# Section3_HW1_Justin_Ngo_u0453732_MotorPC.net
KiCad netlist of a schematic drawn in EAGLE
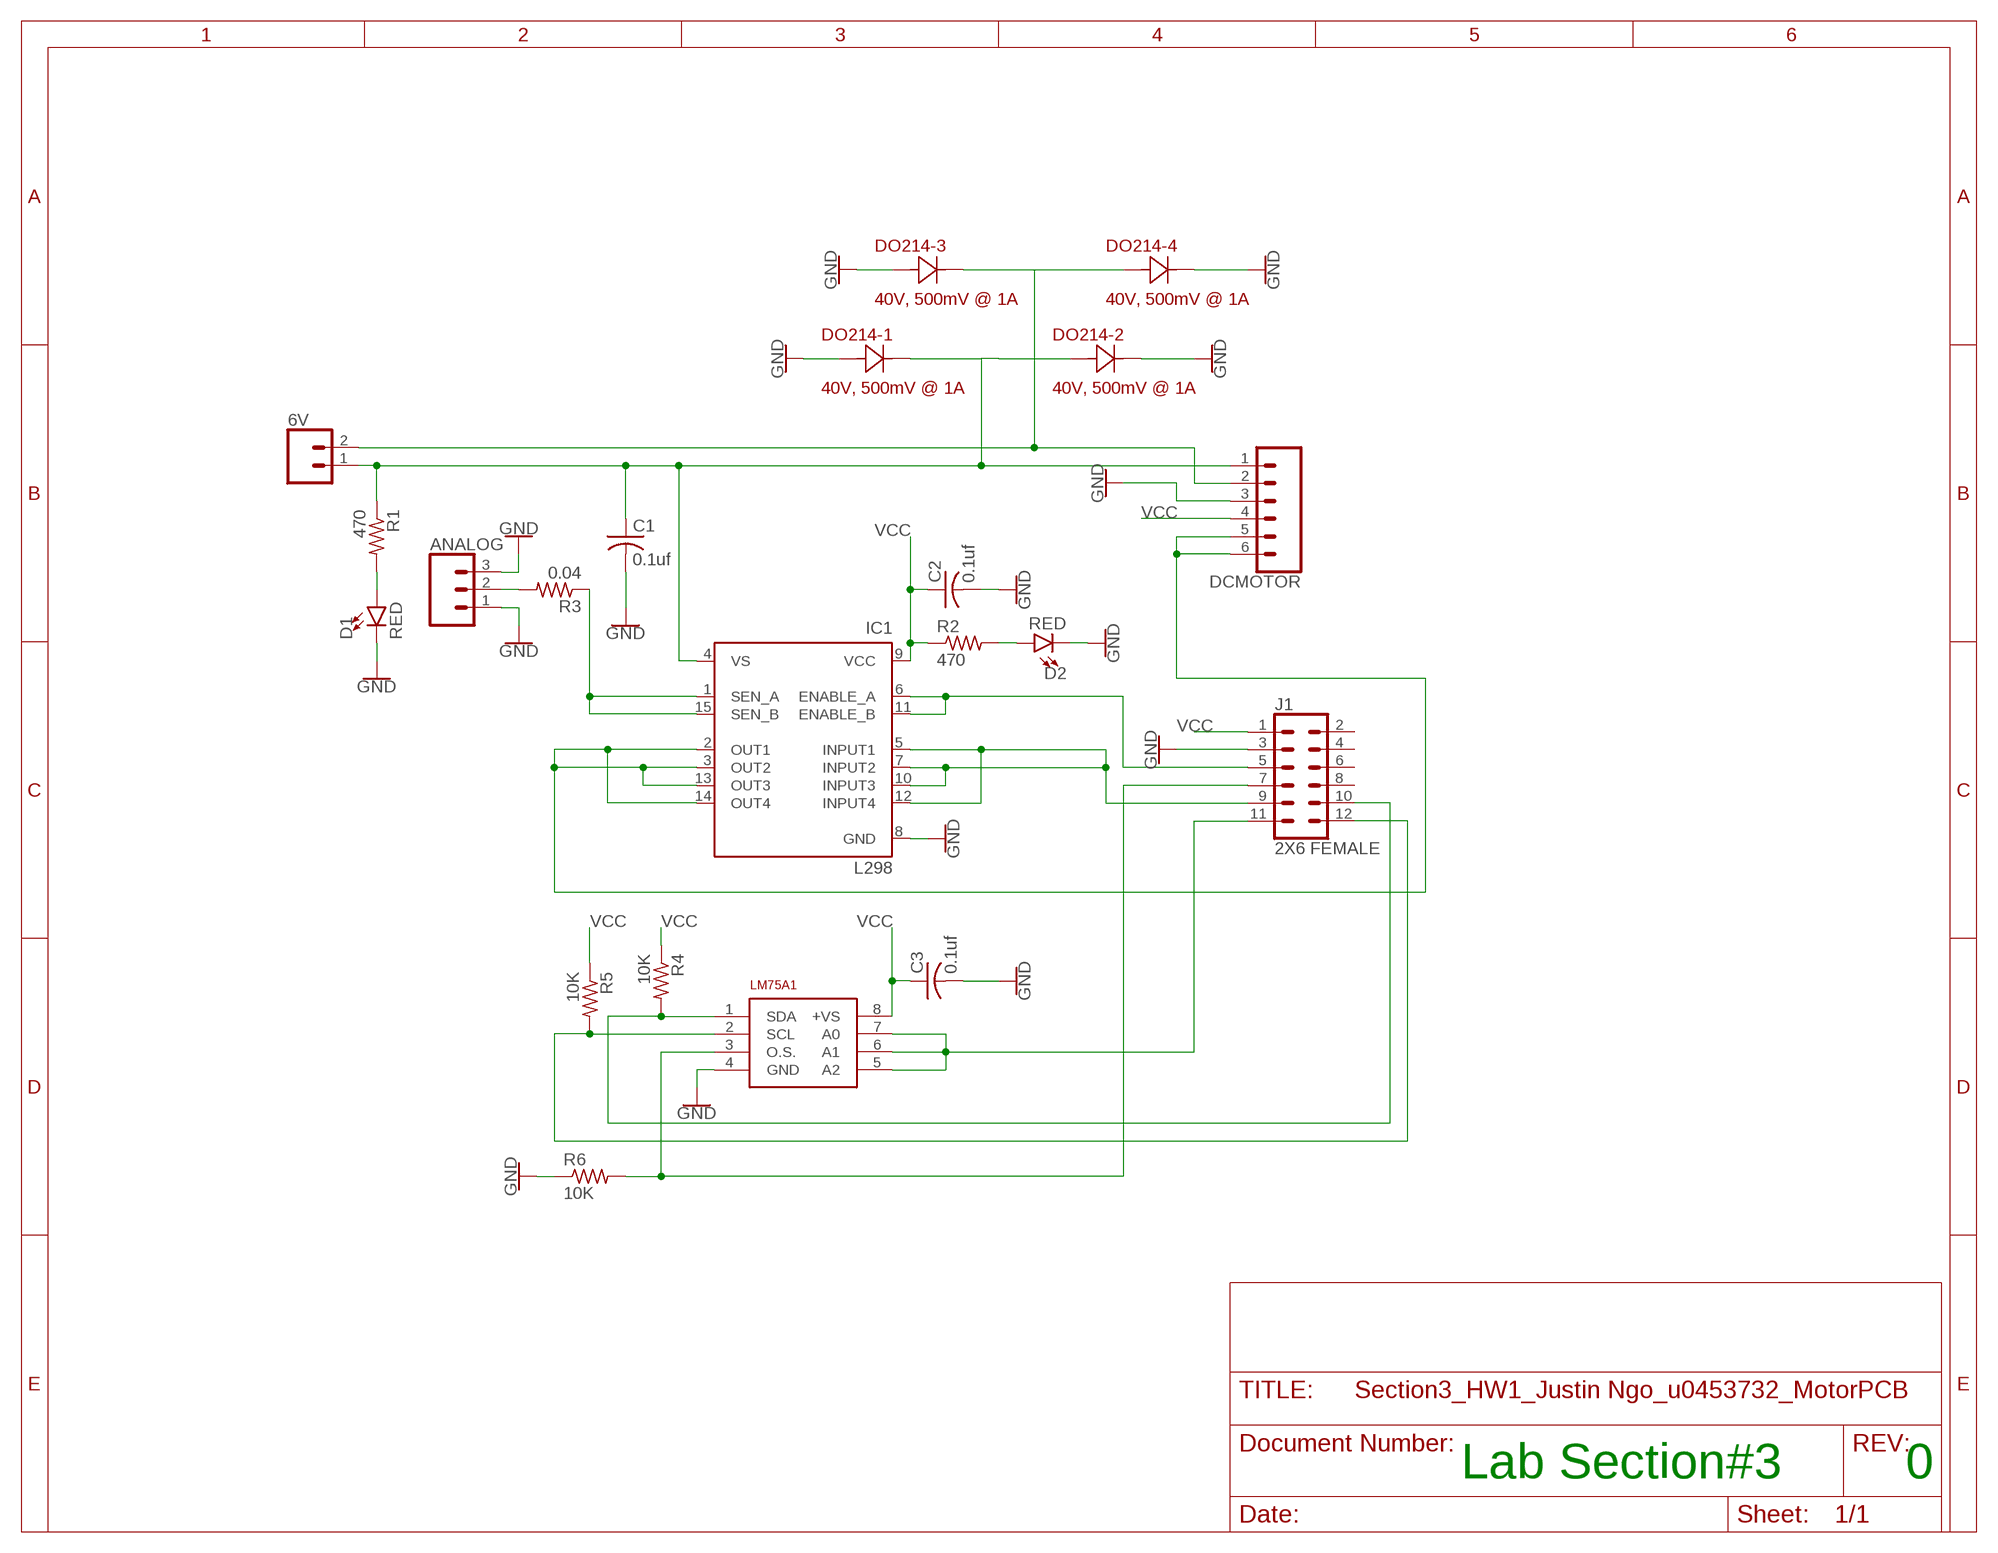
[diagram p0: schematic, sheet 1]

(export (version "E")
  (design (tool "Eeschema 10.0.6"))
  (components
    (comp (ref "6V")
      (value "CONN_025MM")
      (footprint "eagle-import:SCREWTERMINAL-5MM-2")
      (libsource (lib "eagle-import") (part "CONN_025MM"))
    )
    (comp (ref "ANALOG")
      (value "CONN_03")
      (footprint "eagle-import:1X03")
      (libsource (lib "eagle-import") (part "CONN_03"))
    )
    (comp (ref "C1")
      (value "0.1uf")
      (footprint "eagle-import:C1206")
      (libsource (lib "eagle-import") (part "C-USC1206"))
    )
    (comp (ref "C2")
      (value "0.1uf")
      (footprint "eagle-import:C1206")
      (libsource (lib "eagle-import") (part "C-USC1206"))
    )
    (comp (ref "C3")
      (value "0.1uf")
      (footprint "eagle-import:C1206")
      (libsource (lib "eagle-import") (part "C-USC1206"))
    )
    (comp (ref "D1")
      (value "RED")
      (footprint "eagle-import:LED-1206")
      (libsource (lib "eagle-import") (part "LED-RED1206"))
    )
    (comp (ref "D2")
      (value "RED")
      (footprint "eagle-import:LED-1206")
      (libsource (lib "eagle-import") (part "LED-RED1206"))
    )
    (comp (ref "DCMOTOR")
      (value "CONN_06LOCK_LONGPADS")
      (footprint "eagle-import:1X06_LOCK_LONGPADS")
      (libsource (lib "eagle-import") (part "CONN_06LOCK_LONGPADS"))
    )
    (comp (ref "DO214-1")
      (value "40V, 500mV @ 1A")
      (footprint "eagle-import:DIODE_DO214AC")
      (fields
        (field (name "MANUFACTURER_PART_NUMBER") "SS14")
        (field (name "RSPARTNUMBER") "4470352")
        (field (name "COPYRIGHT") "Copyright C 2015 Accelerated Designs. All rights reserved")
      )
      (libsource (lib "eagle-import") (part "SS14"))
    )
    (comp (ref "DO214-2")
      (value "40V, 500mV @ 1A")
      (footprint "eagle-import:DIODE_DO214AC")
      (fields
        (field (name "MANUFACTURER_PART_NUMBER") "SS14")
        (field (name "RSPARTNUMBER") "4470352")
        (field (name "COPYRIGHT") "Copyright C 2015 Accelerated Designs. All rights reserved")
      )
      (libsource (lib "eagle-import") (part "SS14"))
    )
    (comp (ref "DO214-3")
      (value "40V, 500mV @ 1A")
      (footprint "eagle-import:DIODE_DO214AC")
      (fields
        (field (name "MANUFACTURER_PART_NUMBER") "SS14")
        (field (name "RSPARTNUMBER") "4470352")
        (field (name "COPYRIGHT") "Copyright C 2015 Accelerated Designs. All rights reserved")
      )
      (libsource (lib "eagle-import") (part "SS14"))
    )
    (comp (ref "DO214-4")
      (value "40V, 500mV @ 1A")
      (footprint "eagle-import:DIODE_DO214AC")
      (fields
        (field (name "MANUFACTURER_PART_NUMBER") "SS14")
        (field (name "RSPARTNUMBER") "4470352")
        (field (name "COPYRIGHT") "Copyright C 2015 Accelerated Designs. All rights reserved")
      )
      (libsource (lib "eagle-import") (part "SS14"))
    )
    (comp (ref "IC1")
      (value "L298")
      (footprint "eagle-import:MULTIWATT-15")
      (fields (field (name "MPN") "L298N"))
      (libsource (lib "eagle-import") (part "L298"))
    )
    (comp (ref "J1")
      (value "2X6 FEMALE")
      (footprint "eagle-import:2X6")
      (libsource (lib "eagle-import") (part "CONN_06X2PTH_FEMALE"))
    )
    (comp (ref "LM75A1")
      (value "TI-LM75A")
      (footprint "eagle-import:TI-LM75A")
      (libsource (lib "eagle-import") (part "TI-LM75A"))
    )
    (comp (ref "R1")
      (value "470")
      (footprint "eagle-import:R1206")
      (libsource (lib "eagle-import") (part "R-US_R1206"))
    )
    (comp (ref "R2")
      (value "470")
      (footprint "eagle-import:R1206")
      (libsource (lib "eagle-import") (part "R-US_R1206"))
    )
    (comp (ref "R3")
      (value "0.04")
      (footprint "eagle-import:R1206")
      (libsource (lib "eagle-import") (part "R-US_R1206"))
    )
    (comp (ref "R4")
      (value "10K")
      (footprint "eagle-import:R1206")
      (libsource (lib "eagle-import") (part "R-US_R1206"))
    )
    (comp (ref "R5")
      (value "10K")
      (footprint "eagle-import:R1206")
      (libsource (lib "eagle-import") (part "R-US_R1206"))
    )
    (comp (ref "R6")
      (value "10K")
      (footprint "eagle-import:R1206")
      (libsource (lib "eagle-import") (part "R-US_R1206"))
    )
  )
  (nets
    (net (code "1") (name "/VCC") (class "Default")
      (node (ref "C2") (pin "1") (pinfunction "1_1") (pintype "passive"))
      (node (ref "C3") (pin "1") (pinfunction "1_1") (pintype "passive"))
      (node (ref "DCMOTOR") (pin "4") (pinfunction "4_4") (pintype "passive"))
      (node (ref "IC1") (pin "9") (pinfunction "VCC_9") (pintype "power_in"))
      (node (ref "J1") (pin "1") (pinfunction "1_1") (pintype "passive"))
      (node (ref "LM75A1") (pin "8") (pinfunction "+VS_8") (pintype "bidirectional"))
      (node (ref "R2") (pin "1") (pinfunction "1_1") (pintype "passive"))
      (node (ref "R4") (pin "1") (pinfunction "1_1") (pintype "passive"))
      (node (ref "R5") (pin "1") (pinfunction "1_1") (pintype "passive"))
    )
    (net (code "2") (name "GND") (class "Default")
      (node (ref "ANALOG") (pin "1") (pinfunction "1_1") (pintype "passive"))
      (node (ref "ANALOG") (pin "3") (pinfunction "3_3") (pintype "passive"))
      (node (ref "C1") (pin "2") (pinfunction "2_2") (pintype "passive"))
      (node (ref "C2") (pin "2") (pinfunction "2_2") (pintype "passive"))
      (node (ref "C3") (pin "2") (pinfunction "2_2") (pintype "passive"))
      (node (ref "D1") (pin "C") (pinfunction "C_C") (pintype "passive"))
      (node (ref "D2") (pin "C") (pinfunction "C_C") (pintype "passive"))
      (node (ref "DCMOTOR") (pin "3") (pinfunction "3_3") (pintype "passive"))
      (node (ref "DO214-1") (pin "2") (pinfunction "21_2") (pintype "passive"))
      (node (ref "DO214-2") (pin "1") (pinfunction "12_1") (pintype "passive"))
      (node (ref "DO214-3") (pin "2") (pinfunction "21_2") (pintype "passive"))
      (node (ref "DO214-4") (pin "1") (pinfunction "12_1") (pintype "passive"))
      (node (ref "IC1") (pin "8") (pinfunction "GND_8") (pintype "power_in"))
      (node (ref "J1") (pin "3") (pinfunction "3_3") (pintype "passive"))
      (node (ref "LM75A1") (pin "4") (pinfunction "GND_4") (pintype "bidirectional"))
      (node (ref "R6") (pin "1") (pinfunction "1_1") (pintype "passive"))
    )
    (net (code "3") (name "Net-(ANALOG-Pad2)") (class "Default")
      (node (ref "ANALOG") (pin "2") (pinfunction "2_2") (pintype "passive"))
      (node (ref "R3") (pin "2") (pinfunction "2_2") (pintype "passive"))
    )
    (net (code "4") (name "Net-(D1-PadA)") (class "Default")
      (node (ref "D1") (pin "A") (pinfunction "A_A") (pintype "passive"))
      (node (ref "R1") (pin "2") (pinfunction "2_2") (pintype "passive"))
    )
    (net (code "5") (name "Net-(D2-PadA)") (class "Default")
      (node (ref "D2") (pin "A") (pinfunction "A_A") (pintype "passive"))
      (node (ref "R2") (pin "2") (pinfunction "2_2") (pintype "passive"))
    )
    (net (code "6") (name "Net-(DO214-1-12)") (class "Default")
      (node (ref "6V") (pin "1") (pinfunction "1_1") (pintype "passive"))
      (node (ref "C1") (pin "1") (pinfunction "1_1") (pintype "passive"))
      (node (ref "DCMOTOR") (pin "1") (pinfunction "1_1") (pintype "passive"))
      (node (ref "DO214-1") (pin "1") (pinfunction "12_1") (pintype "passive"))
      (node (ref "DO214-2") (pin "2") (pinfunction "21_2") (pintype "passive"))
      (node (ref "IC1") (pin "4") (pinfunction "VS_4") (pintype "power_in"))
      (node (ref "R1") (pin "1") (pinfunction "1_1") (pintype "passive"))
    )
    (net (code "7") (name "Net-(DO214-3-12)") (class "Default")
      (node (ref "6V") (pin "2") (pinfunction "2_2") (pintype "passive"))
      (node (ref "DCMOTOR") (pin "2") (pinfunction "2_2") (pintype "passive"))
      (node (ref "DO214-3") (pin "1") (pinfunction "12_1") (pintype "passive"))
      (node (ref "DO214-4") (pin "2") (pinfunction "21_2") (pintype "passive"))
    )
    (net (code "8") (name "Net-(IC1-ENABLE_A)") (class "Default")
      (node (ref "IC1") (pin "11") (pinfunction "ENABLE_B_11") (pintype "input"))
      (node (ref "IC1") (pin "6") (pinfunction "ENABLE_A_6") (pintype "input"))
      (node (ref "J1") (pin "5") (pinfunction "5_5") (pintype "passive"))
    )
    (net (code "9") (name "Net-(IC1-INPUT1)") (class "Default")
      (node (ref "IC1") (pin "10") (pinfunction "INPUT3_10") (pintype "input"))
      (node (ref "IC1") (pin "12") (pinfunction "INPUT4_12") (pintype "input"))
      (node (ref "IC1") (pin "5") (pinfunction "INPUT1_5") (pintype "input"))
      (node (ref "IC1") (pin "7") (pinfunction "INPUT2_7") (pintype "input"))
      (node (ref "J1") (pin "9") (pinfunction "9_9") (pintype "passive"))
    )
    (net (code "10") (name "Net-(IC1-OUT1)") (class "Default")
      (node (ref "DCMOTOR") (pin "5") (pinfunction "5_5") (pintype "passive"))
      (node (ref "DCMOTOR") (pin "6") (pinfunction "6_6") (pintype "passive"))
      (node (ref "IC1") (pin "13") (pinfunction "OUT3_13") (pintype "output"))
      (node (ref "IC1") (pin "14") (pinfunction "OUT4_14") (pintype "output"))
      (node (ref "IC1") (pin "2") (pinfunction "OUT1_2") (pintype "output"))
      (node (ref "IC1") (pin "3") (pinfunction "OUT2_3") (pintype "output"))
    )
    (net (code "11") (name "Net-(IC1-SEN_A)") (class "Default")
      (node (ref "IC1") (pin "1") (pinfunction "SEN_A_1") (pintype "input"))
      (node (ref "IC1") (pin "15") (pinfunction "SEN_B_15") (pintype "input"))
      (node (ref "R3") (pin "1") (pinfunction "1_1") (pintype "passive"))
    )
    (net (code "12") (name "Net-(LM75A1-A0)") (class "Default")
      (node (ref "J1") (pin "11") (pinfunction "11_11") (pintype "passive"))
      (node (ref "LM75A1") (pin "5") (pinfunction "A2_5") (pintype "bidirectional"))
      (node (ref "LM75A1") (pin "6") (pinfunction "A1_6") (pintype "bidirectional"))
      (node (ref "LM75A1") (pin "7") (pinfunction "A0_7") (pintype "bidirectional"))
    )
    (net (code "13") (name "Net-(LM75A1-O.S.)") (class "Default")
      (node (ref "J1") (pin "7") (pinfunction "7_7") (pintype "passive"))
      (node (ref "LM75A1") (pin "3") (pinfunction "O.S._3") (pintype "bidirectional"))
      (node (ref "R6") (pin "2") (pinfunction "2_2") (pintype "passive"))
    )
    (net (code "14") (name "Net-(LM75A1-SCL)") (class "Default")
      (node (ref "J1") (pin "12") (pinfunction "12_12") (pintype "passive"))
      (node (ref "LM75A1") (pin "2") (pinfunction "SCL_2") (pintype "bidirectional"))
      (node (ref "R5") (pin "2") (pinfunction "2_2") (pintype "passive"))
    )
    (net (code "15") (name "Net-(LM75A1-SDA)") (class "Default")
      (node (ref "J1") (pin "10") (pinfunction "10_10") (pintype "passive"))
      (node (ref "LM75A1") (pin "1") (pinfunction "SDA_1") (pintype "bidirectional"))
      (node (ref "R4") (pin "2") (pinfunction "2_2") (pintype "passive"))
    )
    (net (code "16") (name "unconnected-(J1-Pad2)") (class "Default")
      (node (ref "J1") (pin "2") (pinfunction "2_2") (pintype "passive"))
    )
    (net (code "17") (name "unconnected-(J1-Pad4)") (class "Default")
      (node (ref "J1") (pin "4") (pinfunction "4_4") (pintype "passive"))
    )
    (net (code "18") (name "unconnected-(J1-Pad6)") (class "Default")
      (node (ref "J1") (pin "6") (pinfunction "6_6") (pintype "passive"))
    )
    (net (code "19") (name "unconnected-(J1-Pad8)") (class "Default")
      (node (ref "J1") (pin "8") (pinfunction "8_8") (pintype "passive"))
    )
  )
)
